# fuentes_15V_5V_3_3V.net
KiCad netlist of a schematic drawn in Altium Designer
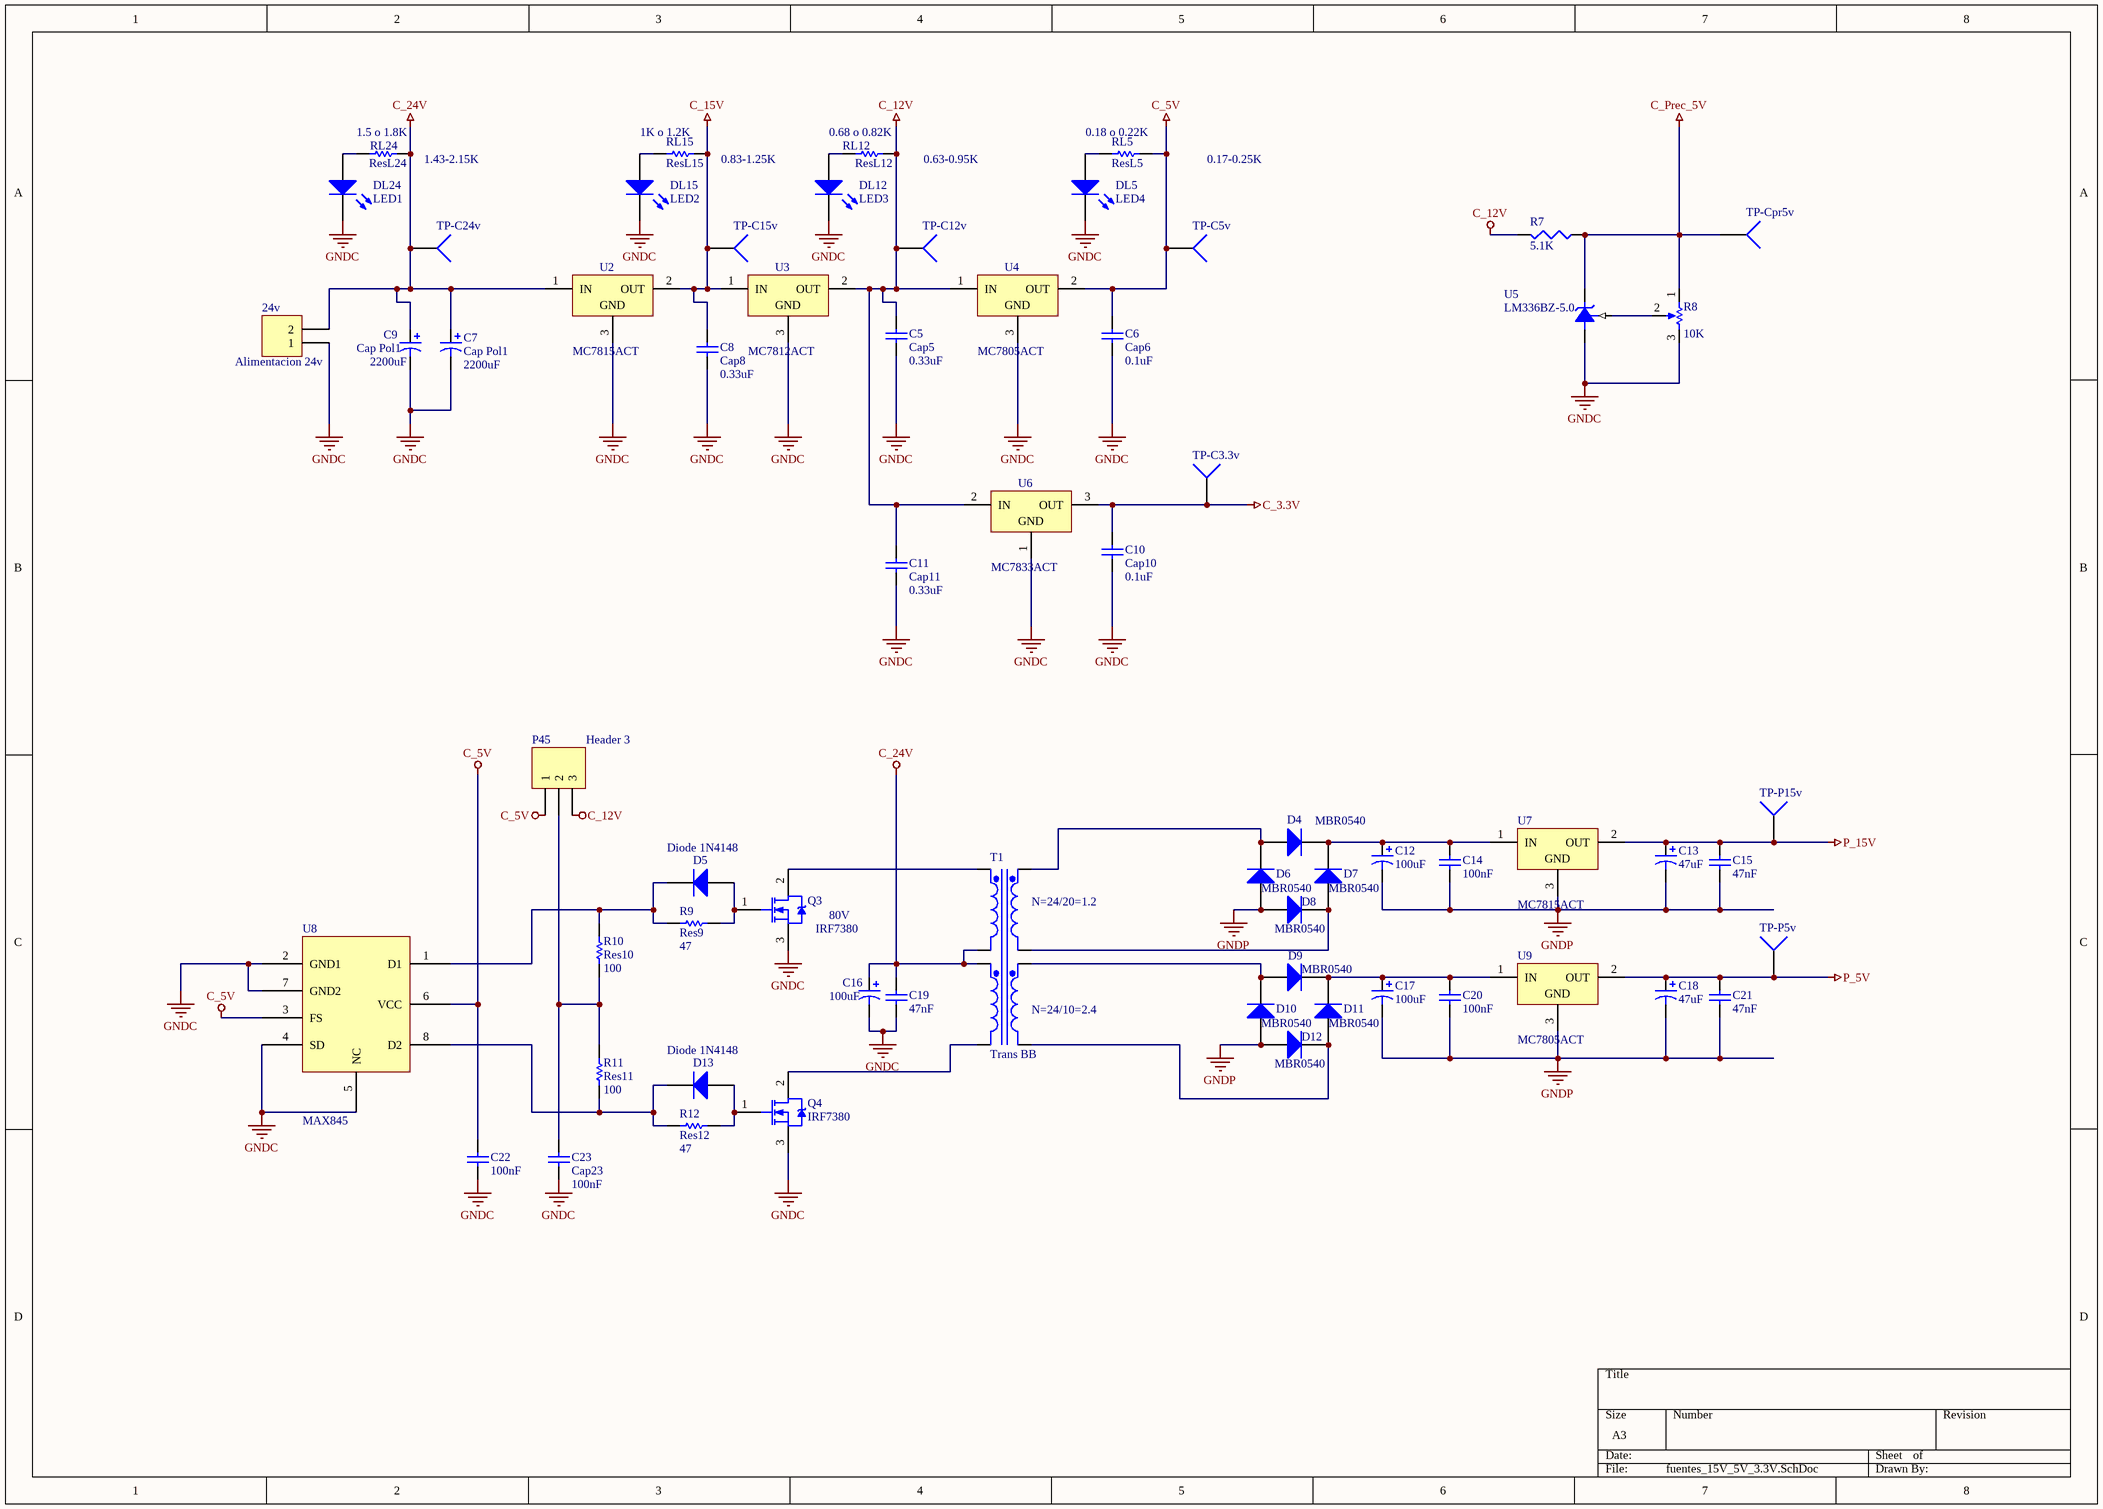
[diagram p0: fuentes_15V_5V_3.3V.SchDoc]

(export (version "E")
  (design (tool "Eeschema 10.0.6"))
  (components
    (comp (ref "24v")
      (value "Alimentacion 24v")
      (footprint "HDR1X2-POT*")
      (description "Header, 2-Pin")
      (fields (field (name "PUBLISHER") "Altium Limited"))
      (libsource (lib "Miscellaneous Connectors") (part "Header 2"))
    )
    (comp (ref "C5")
      (value "Cap5")
      (footprint "8-1206")
      (description "SMD MULTICAPA 50V")
      (fields (field (name "ALTIUM_VALUE") "0.33uF") (field (name "PUBLISHER") "Altium Limited"))
      (libsource (lib "Miscellaneous Devices") (part "Cap"))
    )
    (comp (ref "C6")
      (value "Cap6")
      (footprint "8-1206")
      (description "SMD MULTICAPA 50V")
      (fields (field (name "ALTIUM_VALUE") "0.1uF") (field (name "PUBLISHER") "Altium Limited"))
      (libsource (lib "Miscellaneous Devices") (part "Cap"))
    )
    (comp (ref "C7")
      (value "Cap Pol1")
      (footprint "RB7.6-18.2*")
      (description "Polarized Capacitor (Radial)")
      (fields (field (name "ALTIUM_VALUE") "2200uF") (field (name "PUBLISHER") "Altium Limited"))
      (libsource (lib "Miscellaneous Devices") (part "Cap Pol1"))
    )
    (comp (ref "C8")
      (value "Cap8")
      (footprint "8-1206")
      (description "SMD MULTICAPA 50V")
      (fields (field (name "ALTIUM_VALUE") "0.33uF") (field (name "PUBLISHER") "Altium Limited"))
      (libsource (lib "Miscellaneous Devices") (part "Cap"))
    )
    (comp (ref "C9")
      (value "Cap Pol1")
      (footprint "RB7.6-18.2*")
      (description "Polarized Capacitor (Radial)")
      (fields (field (name "ALTIUM_VALUE") "2200uF") (field (name "PUBLISHER") "Altium Limited"))
      (libsource (lib "Miscellaneous Devices") (part "Cap Pol1"))
    )
    (comp (ref "C10")
      (value "Cap10")
      (footprint "8-1206")
      (description "SMD MULTICAPA 50V")
      (fields (field (name "ALTIUM_VALUE") "0.1uF") (field (name "PUBLISHER") "Altium Limited"))
      (libsource (lib "Miscellaneous Devices") (part "Cap"))
    )
    (comp (ref "C11")
      (value "Cap11")
      (footprint "8-1206")
      (description "SMD MULTICAPA 50V")
      (fields (field (name "ALTIUM_VALUE") "0.33uF") (field (name "PUBLISHER") "Altium Limited"))
      (libsource (lib "Miscellaneous Devices") (part "Cap"))
    )
    (comp (ref "C12")
      (value "100uF")
      (footprint "RB3.5-8*")
      (description "Polarized Capacitor (Radial)")
      (fields (field (name "Comment") "Cap Pol1") (field (name "PUBLISHER") "Altium Limited"))
      (libsource (lib "Miscellaneous Devices") (part "Cap Pol1"))
    )
    (comp (ref "C13")
      (value "47uF")
      (footprint "RB5.8-6.4*")
      (description "Polarized Capacitor (Radial)")
      (fields (field (name "Comment") "Cap Pol1") (field (name "PUBLISHER") "Altium Limited"))
      (libsource (lib "Miscellaneous Devices") (part "Cap Pol1"))
    )
    (comp (ref "C14")
      (value "100nF")
      (footprint "8-1206")
      (description "SMD MULTICAPA 50V")
      (fields (field (name "Comment") "Cap14") (field (name "PUBLISHER") "Altium Limited"))
      (libsource (lib "Miscellaneous Devices") (part "Cap"))
    )
    (comp (ref "C15")
      (value "47nF")
      (footprint "8-1206")
      (description "SMD MULTICAPA 50V")
      (fields (field (name "Comment") "Cap15") (field (name "PUBLISHER") "Altium Limited"))
      (libsource (lib "Miscellaneous Devices") (part "Cap"))
    )
    (comp (ref "C16")
      (value "100uF")
      (footprint "RB3.5-8*")
      (description "Polarized Capacitor (Radial)")
      (fields (field (name "Comment") "Cap Pol1") (field (name "PUBLISHER") "Altium Limited"))
      (libsource (lib "Miscellaneous Devices") (part "Cap Pol1"))
    )
    (comp (ref "C17")
      (value "100uF")
      (footprint "RB3.5-8*")
      (description "Polarized Capacitor (Radial)")
      (fields (field (name "Comment") "Cap Pol1") (field (name "PUBLISHER") "Altium Limited"))
      (libsource (lib "Miscellaneous Devices") (part "Cap Pol1"))
    )
    (comp (ref "C18")
      (value "47uF")
      (footprint "RB5.8-6.4*")
      (description "Polarized Capacitor (Radial)")
      (fields (field (name "Comment") "Cap Pol1") (field (name "PUBLISHER") "Altium Limited"))
      (libsource (lib "Miscellaneous Devices") (part "Cap Pol1"))
    )
    (comp (ref "C19")
      (value "47nF")
      (footprint "8-1206")
      (description "SMD MULTICAPA 50V")
      (fields (field (name "Comment") "Cap19") (field (name "PUBLISHER") "Altium Limited"))
      (libsource (lib "Miscellaneous Devices") (part "Cap"))
    )
    (comp (ref "C20")
      (value "100nF")
      (footprint "8-1206")
      (description "SMD MULTICAPA 50V")
      (fields (field (name "Comment") "Cap20") (field (name "PUBLISHER") "Altium Limited"))
      (libsource (lib "Miscellaneous Devices") (part "Cap"))
    )
    (comp (ref "C21")
      (value "47nF")
      (footprint "8-1206")
      (description "SMD MULTICAPA 50V")
      (fields (field (name "Comment") "Cap21") (field (name "PUBLISHER") "Altium Limited"))
      (libsource (lib "Miscellaneous Devices") (part "Cap"))
    )
    (comp (ref "C22")
      (value "100nF")
      (footprint "8-1206")
      (description "SMD MULTICAPA 50V")
      (fields (field (name "Comment") "Cap22") (field (name "PUBLISHER") "Altium Limited"))
      (libsource (lib "Miscellaneous Devices") (part "Cap"))
    )
    (comp (ref "C23")
      (value "Cap23")
      (footprint "8-1206")
      (description "SMD MULTICAPA 50V")
      (fields (field (name "ALTIUM_VALUE") "100nF") (field (name "PUBLISHER") "Altium Limited"))
      (libsource (lib "Miscellaneous Devices") (part "Cap"))
    )
    (comp (ref "D4")
      (value "MBR0540")
      (footprint "CASE403A*")
      (description "SMD")
      (fields (field (name "PUBLISHER") "Altium Limited"))
      (libsource (lib "Miscellaneous Devices") (part "Diode"))
    )
    (comp (ref "D5")
      (value "Diode 1N4148")
      (footprint "DO-35")
      (description "THRU")
      (fields (field (name "PUBLISHER") "Altium Limited"))
      (libsource (lib "Miscellaneous Devices") (part "Diode 1N4148"))
    )
    (comp (ref "D6")
      (value "MBR0540")
      (footprint "CASE403A*")
      (description "SMD")
      (fields (field (name "PUBLISHER") "Altium Limited"))
      (libsource (lib "Miscellaneous Devices") (part "Diode"))
    )
    (comp (ref "D7")
      (value "MBR0540")
      (footprint "CASE403A*")
      (description "SMD")
      (fields (field (name "PUBLISHER") "Altium Limited"))
      (libsource (lib "Miscellaneous Devices") (part "Diode"))
    )
    (comp (ref "D8")
      (value "MBR0540")
      (footprint "CASE403A*")
      (description "SMD")
      (fields (field (name "PUBLISHER") "Altium Limited"))
      (libsource (lib "Miscellaneous Devices") (part "Diode"))
    )
    (comp (ref "D9")
      (value "MBR0540")
      (footprint "CASE403A*")
      (description "SMD")
      (fields (field (name "PUBLISHER") "Altium Limited"))
      (libsource (lib "Miscellaneous Devices") (part "Diode"))
    )
    (comp (ref "D10")
      (value "MBR0540")
      (footprint "CASE403A*")
      (description "SMD")
      (fields (field (name "PUBLISHER") "Altium Limited"))
      (libsource (lib "Miscellaneous Devices") (part "Diode"))
    )
    (comp (ref "D11")
      (value "MBR0540")
      (footprint "CASE403A*")
      (description "SMD")
      (fields (field (name "PUBLISHER") "Altium Limited"))
      (libsource (lib "Miscellaneous Devices") (part "Diode"))
    )
    (comp (ref "D12")
      (value "MBR0540")
      (footprint "CASE403A*")
      (description "SMD")
      (fields (field (name "PUBLISHER") "Altium Limited"))
      (libsource (lib "Miscellaneous Devices") (part "Diode"))
    )
    (comp (ref "D13")
      (value "Diode 1N4148")
      (footprint "DO-35")
      (description "THRU")
      (fields (field (name "PUBLISHER") "Altium Limited"))
      (libsource (lib "Miscellaneous Devices") (part "Diode 1N4148"))
    )
    (comp (ref "DL5")
      (value "LED4")
      (footprint "LED-1*")
      (description "Typical RED GaAs LED")
      (fields (field (name "PUBLISHER") "Altium Limited"))
      (libsource (lib "Miscellaneous Devices") (part "LED1"))
    )
    (comp (ref "DL12")
      (value "LED3")
      (footprint "LED-1*")
      (description "Typical RED GaAs LED")
      (fields (field (name "PUBLISHER") "Altium Limited"))
      (libsource (lib "Miscellaneous Devices") (part "LED1"))
    )
    (comp (ref "DL15")
      (value "LED2")
      (footprint "LED-1*")
      (description "Typical RED GaAs LED")
      (fields (field (name "PUBLISHER") "Altium Limited"))
      (libsource (lib "Miscellaneous Devices") (part "LED1"))
    )
    (comp (ref "DL24")
      (value "LED1")
      (footprint "LED-1*")
      (description "Typical RED GaAs LED")
      (fields (field (name "PUBLISHER") "Altium Limited"))
      (libsource (lib "Miscellaneous Devices") (part "LED1"))
    )
    (comp (ref "P45")
      (value "Header 3")
      (footprint "HDR1X3*")
      (description "Header, 3-Pin")
      (fields (field (name "PUBLISHER") "Altium Limited"))
      (libsource (lib "Miscellaneous Connectors") (part "Header 3"))
    )
    (comp (ref "Q3")
      (value "IRF7380")
      (footprint "TO220-MOS")
      (description "HEXFET Power MOSFET")
      (fields (field (name "PUBLISHER") "Altium Limited"))
      (libsource (lib "IR Discrete MOSFET - Power") (part "IRFP250"))
    )
    (comp (ref "Q4")
      (value "IRF7380")
      (footprint "TO220-MOS")
      (description "HEXFET Power MOSFET")
      (fields (field (name "PUBLISHER") "Altium Limited"))
      (libsource (lib "IR Discrete MOSFET - Power") (part "IRFP250"))
    )
    (comp (ref "R7")
      (value "5.1K")
      (footprint "AXIAL-0.4")
      (description "Resistor")
      (fields (field (name "Comment") "Res7") (field (name "PUBLISHER") "Altium Limited"))
      (libsource (lib "Miscellaneous Devices") (part "Res3"))
    )
    (comp (ref "R8")
      (value "10K")
      (footprint "VR*")
      (description "PRESET MULTIVUELTA VERTICAL")
      (fields (field (name "Comment") "RPot") (field (name "PUBLISHER") "Altium Limited"))
      (libsource (lib "Miscellaneous Devices") (part "RPot"))
    )
    (comp (ref "R9")
      (value "Res9")
      (footprint "8-1206")
      (description "SMD 1206")
      (fields (field (name "ALTIUM_VALUE") "47") (field (name "PUBLISHER") "Altium Limited"))
      (libsource (lib "Miscellaneous Devices") (part "Res1"))
    )
    (comp (ref "R10")
      (value "Res10")
      (footprint "8-1206")
      (description "Resistor")
      (fields (field (name "ALTIUM_VALUE") "100") (field (name "PUBLISHER") "Altium Limited"))
      (libsource (lib "Miscellaneous Devices") (part "Res1"))
    )
    (comp (ref "R11")
      (value "Res11")
      (footprint "8-1206")
      (description "Resistor")
      (fields (field (name "ALTIUM_VALUE") "100") (field (name "PUBLISHER") "Altium Limited"))
      (libsource (lib "Miscellaneous Devices") (part "Res1"))
    )
    (comp (ref "R12")
      (value "Res12")
      (footprint "8-1206")
      (description "SMD 1206")
      (fields (field (name "ALTIUM_VALUE") "47") (field (name "PUBLISHER") "Altium Limited"))
      (libsource (lib "Miscellaneous Devices") (part "Res1"))
    )
    (comp (ref "RL5")
      (value "ResL5")
      (footprint "8-1206")
      (description "SMD 1206")
      (fields (field (name "ALTIUM_VALUE") "0.18 o 0.22K") (field (name "PUBLISHER") "Altium Limited"))
      (libsource (lib "Miscellaneous Devices") (part "Res1"))
    )
    (comp (ref "RL12")
      (value "ResL12")
      (footprint "8-1206")
      (description "SMD 1206")
      (fields (field (name "ALTIUM_VALUE") "0.68 o 0.82K") (field (name "PUBLISHER") "Altium Limited"))
      (libsource (lib "Miscellaneous Devices") (part "Res1"))
    )
    (comp (ref "RL15")
      (value "ResL15")
      (footprint "8-1206")
      (description "SMD 1206")
      (fields (field (name "ALTIUM_VALUE") "1K o 1.2K") (field (name "PUBLISHER") "Altium Limited"))
      (libsource (lib "Miscellaneous Devices") (part "Res1"))
    )
    (comp (ref "RL24")
      (value "ResL24")
      (footprint "8-1206")
      (description "SMD 1206")
      (fields (field (name "ALTIUM_VALUE") "1.5 o 1.8K") (field (name "PUBLISHER") "Altium Limited"))
      (libsource (lib "Miscellaneous Devices") (part "Res1"))
    )
    (comp (ref "T1")
      (value "Trans BB")
      (footprint "TRAFO-2PRI-2SEC")
      (description "Buck-boost Transformer (Ideal)")
      (fields (field (name "PUBLISHER") "Altium Limited"))
      (libsource (lib "Miscellaneous Devices") (part "Trans BB"))
    )
    (comp (ref "TP-C3.3v")
      (value "~")
      (footprint "PIN1")
      (description "Socket")
      (fields (field (name "PUBLISHER") "Altium Limited"))
      (libsource (lib "Miscellaneous Connectors") (part "Socket"))
    )
    (comp (ref "TP-C5v")
      (value "~")
      (footprint "PIN1")
      (description "Socket")
      (fields (field (name "PUBLISHER") "Altium Limited"))
      (libsource (lib "Miscellaneous Connectors") (part "Socket"))
    )
    (comp (ref "TP-C12v")
      (value "~")
      (footprint "PIN1")
      (description "Socket")
      (fields (field (name "PUBLISHER") "Altium Limited"))
      (libsource (lib "Miscellaneous Connectors") (part "Socket"))
    )
    (comp (ref "TP-C15v")
      (value "~")
      (footprint "PIN1")
      (description "Socket")
      (fields (field (name "PUBLISHER") "Altium Limited"))
      (libsource (lib "Miscellaneous Connectors") (part "Socket"))
    )
    (comp (ref "TP-C24v")
      (value "~")
      (footprint "PIN1")
      (description "Socket")
      (fields (field (name "PUBLISHER") "Altium Limited"))
      (libsource (lib "Miscellaneous Connectors") (part "Socket"))
    )
    (comp (ref "TP-Cpr5v")
      (value "~")
      (footprint "PIN1")
      (description "Socket")
      (fields (field (name "PUBLISHER") "Altium Limited"))
      (libsource (lib "Miscellaneous Connectors") (part "Socket"))
    )
    (comp (ref "TP-P5v")
      (value "~")
      (footprint "PIN1")
      (description "Socket")
      (fields (field (name "PUBLISHER") "Altium Limited"))
      (libsource (lib "Miscellaneous Connectors") (part "Socket"))
    )
    (comp (ref "TP-P15v")
      (value "~")
      (footprint "PIN1")
      (description "Socket")
      (fields (field (name "PUBLISHER") "Altium Limited"))
      (libsource (lib "Miscellaneous Connectors") (part "Socket"))
    )
    (comp (ref "U2")
      (value "MC7815ACT")
      (footprint "TO220*")
      (description "Three-Terminal Positive Voltage Regulator")
      (fields (field (name "PUBLISHER") "Altium Limited"))
      (libsource (lib "ON Semi Power Mgt Voltage Regulator") (part "MC7805ACT"))
    )
    (comp (ref "U3")
      (value "MC7812ACT")
      (footprint "TO220*")
      (description "Three-Terminal Positive Voltage Regulator")
      (fields (field (name "PUBLISHER") "Altium Limited"))
      (libsource (lib "ON Semi Power Mgt Voltage Regulator") (part "MC7805ACT"))
    )
    (comp (ref "U4")
      (value "MC7805ACT")
      (footprint "TO220*")
      (description "Three-Terminal Positive Voltage Regulator")
      (fields (field (name "PUBLISHER") "Altium Limited"))
      (libsource (lib "ON Semi Power Mgt Voltage Regulator") (part "MC7805ACT"))
    )
    (comp (ref "U5")
      (value "LM336BZ-5.0")
      (footprint "Z03A")
      (description "5.0V Reference Diode")
      (fields
        (field (name "MANUFACTURER") "National Semiconductor")
        (field (name "DIGIKEYPARTNUMBER") "LM336BZ-5.0-ND")
        (field (name "PUBLISHER") "Altium Limited")
      )
      (libsource (lib "NSC Voltage Reference") (part "LM336BZ-5.0"))
    )
    (comp (ref "U6")
      (value "MC7833ACT")
      (footprint "TO220*")
      (description "Three-Terminal Positive Voltage Regulator")
      (fields (field (name "PUBLISHER") "Altium Limited"))
      (libsource (lib "") (part "MC7805ACT_1"))
    )
    (comp (ref "U7")
      (value "MC7815ACT")
      (footprint "TO220*")
      (description "Three-Terminal Positive Voltage Regulator")
      (fields (field (name "PUBLISHER") "Altium Limited"))
      (libsource (lib "ON Semi Power Mgt Voltage Regulator") (part "MC7805ACT"))
    )
    (comp (ref "U8") (value "MAX845") (footprint "SO-8") (libsource (lib "IGBT_Modulo_3") (part "MAX845")))
    (comp (ref "U9")
      (value "MC7805ACT")
      (footprint "TO220*")
      (description "Three-Terminal Positive Voltage Regulator")
      (fields (field (name "PUBLISHER") "Altium Limited"))
      (libsource (lib "ON Semi Power Mgt Voltage Regulator") (part "MC7805ACT"))
    )
  )
  (nets
    (net (code "1") (name "C_3.3V") (class "Default")
      (node (ref "C10") (pin "1") (pinfunction "1_1") (pintype "passive"))
      (node (ref "TP-C3.3v") (pin "1") (pinfunction "1_1") (pintype "passive"))
      (node (ref "U6") (pin "3") (pinfunction "OUT_3") (pintype "power_in"))
    )
    (net (code "2") (name "C_5V") (class "Default")
      (node (ref "C22") (pin "2") (pinfunction "2_2") (pintype "passive"))
      (node (ref "C6") (pin "1") (pinfunction "1_1") (pintype "passive"))
      (node (ref "P45") (pin "1") (pinfunction "1_1") (pintype "passive"))
      (node (ref "RL5") (pin "2") (pinfunction "2_2") (pintype "passive"))
      (node (ref "TP-C5v") (pin "1") (pinfunction "1_1") (pintype "passive"))
      (node (ref "U4") (pin "2") (pinfunction "OUT_2") (pintype "power_in"))
      (node (ref "U8") (pin "3") (pinfunction "FS_3") (pintype "passive"))
      (node (ref "U8") (pin "6") (pinfunction "VCC_6") (pintype "passive"))
    )
    (net (code "3") (name "C_12V") (class "Default")
      (node (ref "C11") (pin "1") (pinfunction "1_1") (pintype "passive"))
      (node (ref "C5") (pin "1") (pinfunction "1_1") (pintype "passive"))
      (node (ref "P45") (pin "3") (pinfunction "3_3") (pintype "passive"))
      (node (ref "R7") (pin "2") (pinfunction "2_2") (pintype "passive"))
      (node (ref "RL12") (pin "2") (pinfunction "2_2") (pintype "passive"))
      (node (ref "TP-C12v") (pin "1") (pinfunction "1_1") (pintype "passive"))
      (node (ref "U3") (pin "2") (pinfunction "OUT_2") (pintype "power_in"))
      (node (ref "U4") (pin "1") (pinfunction "IN_1") (pintype "power_in"))
      (node (ref "U6") (pin "2") (pinfunction "IN_2") (pintype "power_in"))
    )
    (net (code "4") (name "C_15V") (class "Default")
      (node (ref "C8") (pin "1") (pinfunction "1_1") (pintype "passive"))
      (node (ref "RL15") (pin "2") (pinfunction "2_2") (pintype "passive"))
      (node (ref "TP-C15v") (pin "1") (pinfunction "1_1") (pintype "passive"))
      (node (ref "U2") (pin "2") (pinfunction "OUT_2") (pintype "power_in"))
      (node (ref "U3") (pin "1") (pinfunction "IN_1") (pintype "power_in"))
    )
    (net (code "5") (name "C_24V") (class "Default")
      (node (ref "24v") (pin "2") (pinfunction "2_2") (pintype "passive"))
      (node (ref "C16") (pin "1") (pinfunction "1_1") (pintype "passive"))
      (node (ref "C19") (pin "2") (pinfunction "2_2") (pintype "passive"))
      (node (ref "C7") (pin "1") (pinfunction "1_1") (pintype "passive"))
      (node (ref "C9") (pin "1") (pinfunction "1_1") (pintype "passive"))
      (node (ref "RL24") (pin "2") (pinfunction "2_2") (pintype "passive"))
      (node (ref "T1") (pin "2") (pinfunction "Pri1-_2") (pintype "passive"))
      (node (ref "T1") (pin "3") (pinfunction "Pri2+_3") (pintype "passive"))
      (node (ref "TP-C24v") (pin "1") (pinfunction "1_1") (pintype "passive"))
      (node (ref "U2") (pin "1") (pinfunction "IN_1") (pintype "power_in"))
    )
    (net (code "6") (name "C_Prec_5V") (class "Default")
      (node (ref "R7") (pin "1") (pinfunction "1_1") (pintype "passive"))
      (node (ref "R8") (pin "1") (pinfunction "TOP_1") (pintype "passive"))
      (node (ref "TP-Cpr5v") (pin "1") (pinfunction "1_1") (pintype "passive"))
      (node (ref "U5") (pin "2") (pinfunction "+V_2") (pintype "passive"))
    )
    (net (code "7") (name "GNDC") (class "Default")
      (node (ref "24v") (pin "1") (pinfunction "1_1") (pintype "passive"))
      (node (ref "C10") (pin "2") (pinfunction "2_2") (pintype "passive"))
      (node (ref "C11") (pin "2") (pinfunction "2_2") (pintype "passive"))
      (node (ref "C16") (pin "2") (pinfunction "2_2") (pintype "passive"))
      (node (ref "C19") (pin "1") (pinfunction "1_1") (pintype "passive"))
      (node (ref "C22") (pin "1") (pinfunction "1_1") (pintype "passive"))
      (node (ref "C23") (pin "2") (pinfunction "2_2") (pintype "passive"))
      (node (ref "C5") (pin "2") (pinfunction "2_2") (pintype "passive"))
      (node (ref "C6") (pin "2") (pinfunction "2_2") (pintype "passive"))
      (node (ref "C7") (pin "2") (pinfunction "2_2") (pintype "passive"))
      (node (ref "C8") (pin "2") (pinfunction "2_2") (pintype "passive"))
      (node (ref "C9") (pin "2") (pinfunction "2_2") (pintype "passive"))
      (node (ref "DL12") (pin "2") (pinfunction "K_2") (pintype "passive"))
      (node (ref "DL15") (pin "2") (pinfunction "K_2") (pintype "passive"))
      (node (ref "DL24") (pin "2") (pinfunction "K_2") (pintype "passive"))
      (node (ref "DL5") (pin "2") (pinfunction "K_2") (pintype "passive"))
      (node (ref "Q3") (pin "3") (pinfunction "S_3") (pintype "passive"))
      (node (ref "Q4") (pin "3") (pinfunction "S_3") (pintype "passive"))
      (node (ref "R8") (pin "3") (pinfunction "BOT_3") (pintype "passive"))
      (node (ref "U2") (pin "3") (pinfunction "GND_3") (pintype "power_in"))
      (node (ref "U3") (pin "3") (pinfunction "GND_3") (pintype "power_in"))
      (node (ref "U4") (pin "3") (pinfunction "GND_3") (pintype "power_in"))
      (node (ref "U5") (pin "1") (pinfunction "-V_1") (pintype "passive"))
      (node (ref "U6") (pin "1") (pinfunction "GND_1") (pintype "power_in"))
      (node (ref "U8") (pin "2") (pinfunction "GND1_2") (pintype "passive"))
      (node (ref "U8") (pin "4") (pinfunction "SD_4") (pintype "passive"))
      (node (ref "U8") (pin "5") (pinfunction "NC_5") (pintype "passive"))
      (node (ref "U8") (pin "7") (pinfunction "GND2_7") (pintype "passive"))
    )
    (net (code "8") (name "GNDP") (class "Default")
      (node (ref "C12") (pin "2") (pinfunction "2_2") (pintype "passive"))
      (node (ref "C13") (pin "2") (pinfunction "2_2") (pintype "passive"))
      (node (ref "C14") (pin "1") (pinfunction "1_1") (pintype "passive"))
      (node (ref "C15") (pin "1") (pinfunction "1_1") (pintype "passive"))
      (node (ref "C17") (pin "2") (pinfunction "2_2") (pintype "passive"))
      (node (ref "C18") (pin "2") (pinfunction "2_2") (pintype "passive"))
      (node (ref "C20") (pin "1") (pinfunction "1_1") (pintype "passive"))
      (node (ref "C21") (pin "1") (pinfunction "1_1") (pintype "passive"))
      (node (ref "D10") (pin "1") (pinfunction "A_1") (pintype "passive"))
      (node (ref "D12") (pin "1") (pinfunction "A_1") (pintype "passive"))
      (node (ref "D6") (pin "1") (pinfunction "A_1") (pintype "passive"))
      (node (ref "D8") (pin "1") (pinfunction "A_1") (pintype "passive"))
      (node (ref "U7") (pin "3") (pinfunction "GND_3") (pintype "power_in"))
      (node (ref "U9") (pin "3") (pinfunction "GND_3") (pintype "power_in"))
    )
    (net (code "9") (name "Net-(C23-Pad1)") (class "Default")
      (node (ref "C23") (pin "1") (pinfunction "1_1") (pintype "passive"))
      (node (ref "P45") (pin "2") (pinfunction "2_2") (pintype "passive"))
      (node (ref "R10") (pin "2") (pinfunction "2_2") (pintype "passive"))
      (node (ref "R11") (pin "1") (pinfunction "1_1") (pintype "passive"))
    )
    (net (code "10") (name "Net-(D4-A)") (class "Default")
      (node (ref "D4") (pin "1") (pinfunction "A_1") (pintype "passive"))
      (node (ref "D6") (pin "2") (pinfunction "K_2") (pintype "passive"))
      (node (ref "T1") (pin "5") (pinfunction "Sec1+_5") (pintype "passive"))
    )
    (net (code "11") (name "Net-(D4-K)") (class "Default")
      (node (ref "C12") (pin "1") (pinfunction "1_1") (pintype "passive"))
      (node (ref "C14") (pin "2") (pinfunction "2_2") (pintype "passive"))
      (node (ref "D4") (pin "2") (pinfunction "K_2") (pintype "passive"))
      (node (ref "D7") (pin "2") (pinfunction "K_2") (pintype "passive"))
      (node (ref "U7") (pin "1") (pinfunction "IN_1") (pintype "power_in"))
    )
    (net (code "12") (name "Net-(D5-A)") (class "Default")
      (node (ref "D5") (pin "1") (pinfunction "A_1") (pintype "passive"))
      (node (ref "Q3") (pin "1") (pinfunction "G_1") (pintype "passive"))
      (node (ref "R9") (pin "2") (pinfunction "2_2") (pintype "passive"))
    )
    (net (code "13") (name "Net-(D5-K)") (class "Default")
      (node (ref "D5") (pin "2") (pinfunction "K_2") (pintype "passive"))
      (node (ref "R10") (pin "1") (pinfunction "1_1") (pintype "passive"))
      (node (ref "R9") (pin "1") (pinfunction "1_1") (pintype "passive"))
      (node (ref "U8") (pin "1") (pinfunction "D1_1") (pintype "passive"))
    )
    (net (code "14") (name "Net-(D7-A)") (class "Default")
      (node (ref "D7") (pin "1") (pinfunction "A_1") (pintype "passive"))
      (node (ref "D8") (pin "2") (pinfunction "K_2") (pintype "passive"))
      (node (ref "T1") (pin "6") (pinfunction "Sec1-_6") (pintype "passive"))
    )
    (net (code "15") (name "Net-(D10-K)") (class "Default")
      (node (ref "D10") (pin "2") (pinfunction "K_2") (pintype "passive"))
      (node (ref "D9") (pin "1") (pinfunction "A_1") (pintype "passive"))
      (node (ref "T1") (pin "7") (pinfunction "Sec2+_7") (pintype "passive"))
    )
    (net (code "16") (name "Net-(D11-A)") (class "Default")
      (node (ref "D11") (pin "1") (pinfunction "A_1") (pintype "passive"))
      (node (ref "D12") (pin "2") (pinfunction "K_2") (pintype "passive"))
      (node (ref "T1") (pin "8") (pinfunction "Sec2-_8") (pintype "passive"))
    )
    (net (code "17") (name "Net-(D11-K)") (class "Default")
      (node (ref "C17") (pin "1") (pinfunction "1_1") (pintype "passive"))
      (node (ref "C20") (pin "2") (pinfunction "2_2") (pintype "passive"))
      (node (ref "D11") (pin "2") (pinfunction "K_2") (pintype "passive"))
      (node (ref "D9") (pin "2") (pinfunction "K_2") (pintype "passive"))
      (node (ref "U9") (pin "1") (pinfunction "IN_1") (pintype "power_in"))
    )
    (net (code "18") (name "Net-(D13-A)") (class "Default")
      (node (ref "D13") (pin "1") (pinfunction "A_1") (pintype "passive"))
      (node (ref "Q4") (pin "1") (pinfunction "G_1") (pintype "passive"))
      (node (ref "R12") (pin "2") (pinfunction "2_2") (pintype "passive"))
    )
    (net (code "19") (name "Net-(D13-K)") (class "Default")
      (node (ref "D13") (pin "2") (pinfunction "K_2") (pintype "passive"))
      (node (ref "R11") (pin "2") (pinfunction "2_2") (pintype "passive"))
      (node (ref "R12") (pin "1") (pinfunction "1_1") (pintype "passive"))
      (node (ref "U8") (pin "8") (pinfunction "D2_8") (pintype "passive"))
    )
    (net (code "20") (name "Net-(DL5-A)") (class "Default")
      (node (ref "DL5") (pin "1") (pinfunction "A_1") (pintype "passive"))
      (node (ref "RL5") (pin "1") (pinfunction "1_1") (pintype "passive"))
    )
    (net (code "21") (name "Net-(DL12-A)") (class "Default")
      (node (ref "DL12") (pin "1") (pinfunction "A_1") (pintype "passive"))
      (node (ref "RL12") (pin "1") (pinfunction "1_1") (pintype "passive"))
    )
    (net (code "22") (name "Net-(DL15-A)") (class "Default")
      (node (ref "DL15") (pin "1") (pinfunction "A_1") (pintype "passive"))
      (node (ref "RL15") (pin "1") (pinfunction "1_1") (pintype "passive"))
    )
    (net (code "23") (name "Net-(DL24-A)") (class "Default")
      (node (ref "DL24") (pin "1") (pinfunction "A_1") (pintype "passive"))
      (node (ref "RL24") (pin "1") (pinfunction "1_1") (pintype "passive"))
    )
    (net (code "24") (name "Net-(Q3-D)") (class "Default")
      (node (ref "Q3") (pin "2") (pinfunction "D_2") (pintype "passive"))
      (node (ref "T1") (pin "1") (pinfunction "Pri1+_1") (pintype "passive"))
    )
    (net (code "25") (name "Net-(Q4-D)") (class "Default")
      (node (ref "Q4") (pin "2") (pinfunction "D_2") (pintype "passive"))
      (node (ref "T1") (pin "4") (pinfunction "Pri2-_4") (pintype "passive"))
    )
    (net (code "26") (name "Net-(R8-TAP)") (class "Default")
      (node (ref "R8") (pin "2") (pinfunction "TAP_2") (pintype "passive"))
      (node (ref "U5") (pin "3") (pinfunction "ADJ_3") (pintype "input"))
    )
    (net (code "27") (name "P_5V") (class "Default")
      (node (ref "C18") (pin "1") (pinfunction "1_1") (pintype "passive"))
      (node (ref "C21") (pin "2") (pinfunction "2_2") (pintype "passive"))
      (node (ref "TP-P5v") (pin "1") (pinfunction "1_1") (pintype "passive"))
      (node (ref "U9") (pin "2") (pinfunction "OUT_2") (pintype "power_in"))
    )
    (net (code "28") (name "P_15V") (class "Default")
      (node (ref "C13") (pin "1") (pinfunction "1_1") (pintype "passive"))
      (node (ref "C15") (pin "2") (pinfunction "2_2") (pintype "passive"))
      (node (ref "TP-P15v") (pin "1") (pinfunction "1_1") (pintype "passive"))
      (node (ref "U7") (pin "2") (pinfunction "OUT_2") (pintype "power_in"))
    )
  )
)
